# ControlBoardEspV2.net
KiCad netlist of a schematic drawn in EAGLE
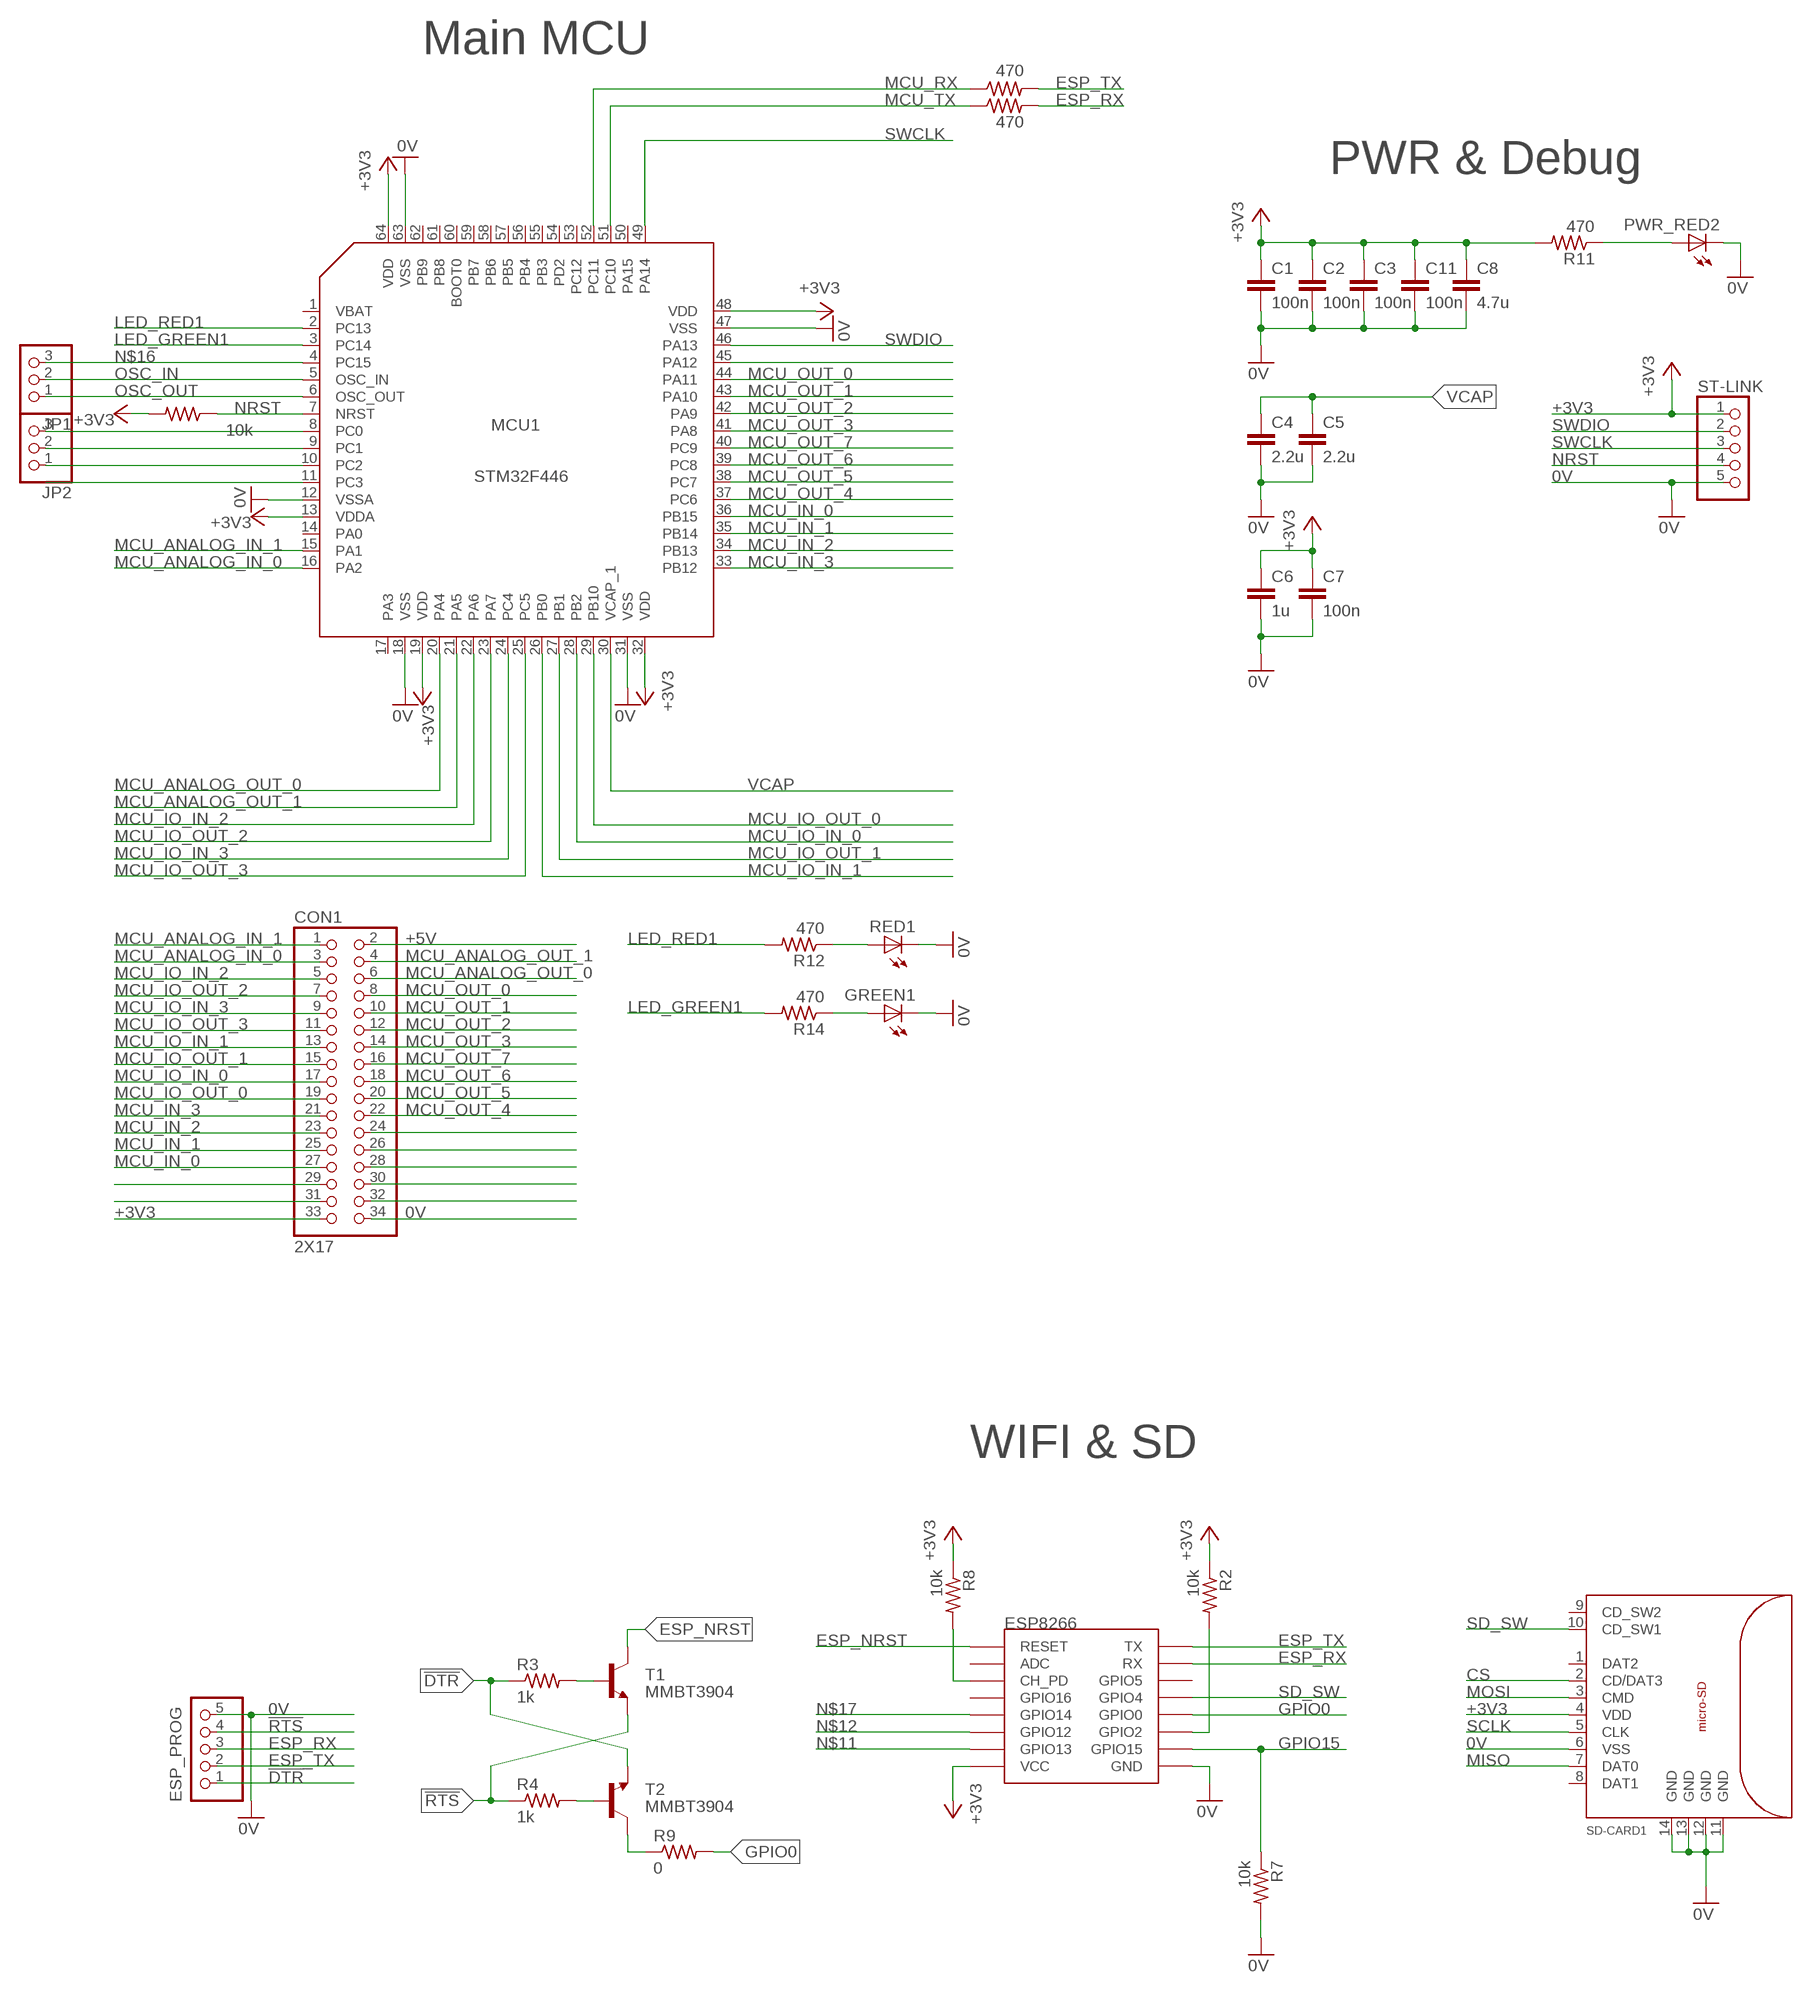
[diagram p0: schematic, sheet 1]

(export (version "E")
  (design (tool "Eeschema 10.0.6"))
  (components
    (comp (ref "C1")
      (value "100n")
      (footprint "eagle-import:C0402")
      (libsource (lib "eagle-import") (part "C-EUC0402"))
    )
    (comp (ref "C2")
      (value "100n")
      (footprint "eagle-import:C0402")
      (libsource (lib "eagle-import") (part "C-EUC0402"))
    )
    (comp (ref "C3")
      (value "100n")
      (footprint "eagle-import:C0402")
      (libsource (lib "eagle-import") (part "C-EUC0402"))
    )
    (comp (ref "C4")
      (value "2.2u")
      (footprint "eagle-import:C0402")
      (libsource (lib "eagle-import") (part "C-EUC0402"))
    )
    (comp (ref "C5")
      (value "2.2u")
      (footprint "eagle-import:C0402")
      (libsource (lib "eagle-import") (part "C-EUC0402"))
    )
    (comp (ref "C6")
      (value "1u")
      (footprint "eagle-import:C0402")
      (libsource (lib "eagle-import") (part "C-EUC0402"))
    )
    (comp (ref "C7")
      (value "100n")
      (footprint "eagle-import:C0402")
      (libsource (lib "eagle-import") (part "C-EUC0402"))
    )
    (comp (ref "C8")
      (value "4.7u")
      (footprint "eagle-import:C0402")
      (libsource (lib "eagle-import") (part "C-EUC0402"))
    )
    (comp (ref "C11")
      (value "100n")
      (footprint "eagle-import:C0402")
      (libsource (lib "eagle-import") (part "C-EUC0402"))
    )
    (comp (ref "CON1")
      (value "2X17")
      (footprint "eagle-import:2X17")
      (libsource (lib "eagle-import") (part "2X17"))
    )
    (comp (ref "ESP8266")
      (value "ESP12SMD")
      (footprint "eagle-import:ESP12-SMD")
      (libsource (lib "eagle-import") (part "ESP12SMD"))
    )
    (comp (ref "ESP_PROG")
      (value "PINHD-1X5")
      (footprint "eagle-import:1X05")
      (libsource (lib "eagle-import") (part "PINHD-1X5"))
    )
    (comp (ref "GREEN1")
      (value "LEDCHIP-LED0805")
      (footprint "eagle-import:CHIP-LED0805")
      (libsource (lib "eagle-import") (part "LEDCHIP-LED0805"))
    )
    (comp (ref "JP1")
      (value "PINHD-1X3")
      (footprint "eagle-import:1X03")
      (libsource (lib "eagle-import") (part "PINHD-1X3"))
    )
    (comp (ref "JP2")
      (value "PINHD-1X3")
      (footprint "eagle-import:1X03")
      (libsource (lib "eagle-import") (part "PINHD-1X3"))
    )
    (comp (ref "MCU1")
      (value "STM32F446")
      (footprint "eagle-import:LQFP-64")
      (libsource (lib "eagle-import") (part "STM32F446"))
    )
    (comp (ref "PWR_RED2")
      (value "LEDCHIP-LED0805")
      (footprint "eagle-import:CHIP-LED0805")
      (libsource (lib "eagle-import") (part "LEDCHIP-LED0805"))
    )
    (comp (ref "R1")
      (value "10k")
      (footprint "eagle-import:R0402")
      (libsource (lib "eagle-import") (part "R-US_R0402"))
    )
    (comp (ref "R2")
      (value "10k")
      (footprint "eagle-import:R0402")
      (libsource (lib "eagle-import") (part "R-US_R0402"))
    )
    (comp (ref "R3")
      (value "1k")
      (footprint "eagle-import:R0402")
      (libsource (lib "eagle-import") (part "R-US_R0402"))
    )
    (comp (ref "R4")
      (value "1k")
      (footprint "eagle-import:R1206")
      (libsource (lib "eagle-import") (part "R-US_R1206"))
    )
    (comp (ref "R5")
      (value "470")
      (footprint "eagle-import:R0402")
      (libsource (lib "eagle-import") (part "R-US_R0402"))
    )
    (comp (ref "R6")
      (value "470")
      (footprint "eagle-import:R0402")
      (libsource (lib "eagle-import") (part "R-US_R0402"))
    )
    (comp (ref "R7")
      (value "10k")
      (footprint "eagle-import:R0402")
      (libsource (lib "eagle-import") (part "R-US_R0402"))
    )
    (comp (ref "R8")
      (value "10k")
      (footprint "eagle-import:R0402")
      (libsource (lib "eagle-import") (part "R-US_R0402"))
    )
    (comp (ref "R9")
      (value "0")
      (footprint "eagle-import:R1206")
      (libsource (lib "eagle-import") (part "R-US_R1206"))
    )
    (comp (ref "R11")
      (value "470")
      (footprint "eagle-import:R0402")
      (libsource (lib "eagle-import") (part "R-US_R0402"))
    )
    (comp (ref "R12")
      (value "470")
      (footprint "eagle-import:R0402")
      (libsource (lib "eagle-import") (part "R-US_R0402"))
    )
    (comp (ref "R14")
      (value "470")
      (footprint "eagle-import:R0402")
      (libsource (lib "eagle-import") (part "R-US_R0402"))
    )
    (comp (ref "RED1")
      (value "LEDCHIP-LED0805")
      (footprint "eagle-import:CHIP-LED0805")
      (libsource (lib "eagle-import") (part "LEDCHIP-LED0805"))
    )
    (comp (ref "SD-CARD1")
      (value "MICRO-SD")
      (footprint "eagle-import:MICRO_SD_FOOTPRINT")
      (libsource (lib "eagle-import") (part "MICRO-SD"))
    )
    (comp (ref "ST-LINK")
      (value "PINHD-1X5")
      (footprint "eagle-import:1X05")
      (libsource (lib "eagle-import") (part "PINHD-1X5"))
    )
    (comp (ref "T1")
      (value "MMBT3904")
      (footprint "eagle-import:SOT23-BEC")
      (libsource (lib "eagle-import") (part "-NPN-SOT23-BECMMBT3904LT1"))
    )
    (comp (ref "T2")
      (value "MMBT3904")
      (footprint "eagle-import:SOT23-BEC")
      (libsource (lib "eagle-import") (part "-NPN-SOT23-BECMMBT3904LT1"))
    )
  )
  (nets
    (net (code "1") (name "+3V3") (class "Default")
      (node (ref "C1") (pin "1") (pinfunction "1_1") (pintype "passive"))
      (node (ref "C11") (pin "1") (pinfunction "1_1") (pintype "passive"))
      (node (ref "C2") (pin "1") (pinfunction "1_1") (pintype "passive"))
      (node (ref "C3") (pin "1") (pinfunction "1_1") (pintype "passive"))
      (node (ref "C6") (pin "1") (pinfunction "1_1") (pintype "passive"))
      (node (ref "C7") (pin "1") (pinfunction "1_1") (pintype "passive"))
      (node (ref "C8") (pin "1") (pinfunction "1_1") (pintype "passive"))
      (node (ref "CON1") (pin "33") (pinfunction "33_33") (pintype "passive"))
      (node (ref "ESP8266") (pin "VCC") (pinfunction "VCC_VCC") (pintype "bidirectional"))
      (node (ref "MCU1") (pin "13") (pinfunction "VDDA_13") (pintype "bidirectional"))
      (node (ref "MCU1") (pin "19") (pinfunction "VDD_19") (pintype "bidirectional"))
      (node (ref "MCU1") (pin "32") (pinfunction "VDD_32") (pintype "bidirectional"))
      (node (ref "MCU1") (pin "48") (pinfunction "VDD_48") (pintype "bidirectional"))
      (node (ref "MCU1") (pin "64") (pinfunction "VDD_64") (pintype "bidirectional"))
      (node (ref "R1") (pin "2") (pinfunction "2_2") (pintype "passive"))
      (node (ref "R11") (pin "2") (pinfunction "2_2") (pintype "passive"))
      (node (ref "R2") (pin "1") (pinfunction "1_1") (pintype "passive"))
      (node (ref "R8") (pin "1") (pinfunction "1_1") (pintype "passive"))
      (node (ref "SD-CARD1") (pin "4") (pinfunction "VDD_4") (pintype "bidirectional"))
      (node (ref "ST-LINK") (pin "1") (pinfunction "1_1") (pintype "passive"))
    )
    (net (code "2") (name "/+5V") (class "Default")
      (node (ref "CON1") (pin "2") (pinfunction "2_2") (pintype "passive"))
    )
    (net (code "3") (name "/CS") (class "Default")
      (node (ref "SD-CARD1") (pin "2") (pinfunction "CD/DAT3_2") (pintype "bidirectional"))
    )
    (net (code "4") (name "/ESP_RX") (class "Default")
      (node (ref "ESP8266") (pin "RXD0") (pinfunction "RX_RXD0") (pintype "bidirectional"))
      (node (ref "ESP_PROG") (pin "3") (pinfunction "3_3") (pintype "passive"))
      (node (ref "R6") (pin "2") (pinfunction "2_2") (pintype "passive"))
    )
    (net (code "5") (name "/ESP_TX") (class "Default")
      (node (ref "ESP8266") (pin "TXD0") (pinfunction "TX_TXD0") (pintype "bidirectional"))
      (node (ref "ESP_PROG") (pin "2") (pinfunction "2_2") (pintype "passive"))
      (node (ref "R5") (pin "2") (pinfunction "2_2") (pintype "passive"))
    )
    (net (code "6") (name "/GPIO15") (class "Default")
      (node (ref "ESP8266") (pin "GPIO15") (pinfunction "GPIO15_GPIO15") (pintype "bidirectional"))
      (node (ref "R7") (pin "1") (pinfunction "1_1") (pintype "passive"))
    )
    (net (code "7") (name "/LED_GREEN1") (class "Default")
      (node (ref "MCU1") (pin "3") (pinfunction "PC14_3") (pintype "bidirectional"))
      (node (ref "R14") (pin "2") (pinfunction "2_2") (pintype "passive"))
    )
    (net (code "8") (name "/LED_RED1") (class "Default")
      (node (ref "MCU1") (pin "2") (pinfunction "PC13_2") (pintype "bidirectional"))
      (node (ref "R12") (pin "2") (pinfunction "2_2") (pintype "passive"))
    )
    (net (code "9") (name "/MCU_ANALOG_IN_0") (class "Default")
      (node (ref "CON1") (pin "3") (pinfunction "3_3") (pintype "passive"))
      (node (ref "MCU1") (pin "16") (pinfunction "PA2_16") (pintype "bidirectional"))
    )
    (net (code "10") (name "/MCU_ANALOG_IN_1") (class "Default")
      (node (ref "CON1") (pin "1") (pinfunction "1_1") (pintype "passive"))
      (node (ref "MCU1") (pin "15") (pinfunction "PA1_15") (pintype "bidirectional"))
    )
    (net (code "11") (name "/MCU_ANALOG_OUT_0") (class "Default")
      (node (ref "CON1") (pin "6") (pinfunction "6_6") (pintype "passive"))
      (node (ref "MCU1") (pin "20") (pinfunction "PA4_20") (pintype "bidirectional"))
    )
    (net (code "12") (name "/MCU_ANALOG_OUT_1") (class "Default")
      (node (ref "CON1") (pin "4") (pinfunction "4_4") (pintype "passive"))
      (node (ref "MCU1") (pin "21") (pinfunction "PA5_21") (pintype "bidirectional"))
    )
    (net (code "13") (name "/MCU_IN_0") (class "Default")
      (node (ref "CON1") (pin "27") (pinfunction "27_27") (pintype "passive"))
      (node (ref "MCU1") (pin "36") (pinfunction "PB15_36") (pintype "bidirectional"))
    )
    (net (code "14") (name "/MCU_IN_1") (class "Default")
      (node (ref "CON1") (pin "25") (pinfunction "25_25") (pintype "passive"))
      (node (ref "MCU1") (pin "35") (pinfunction "PB14_35") (pintype "bidirectional"))
    )
    (net (code "15") (name "/MCU_IN_2") (class "Default")
      (node (ref "CON1") (pin "23") (pinfunction "23_23") (pintype "passive"))
      (node (ref "MCU1") (pin "34") (pinfunction "PB13_34") (pintype "bidirectional"))
    )
    (net (code "16") (name "/MCU_IN_3") (class "Default")
      (node (ref "CON1") (pin "21") (pinfunction "21_21") (pintype "passive"))
      (node (ref "MCU1") (pin "33") (pinfunction "PB12_33") (pintype "bidirectional"))
    )
    (net (code "17") (name "/MCU_IO_IN_0") (class "Default")
      (node (ref "CON1") (pin "17") (pinfunction "17_17") (pintype "passive"))
      (node (ref "MCU1") (pin "28") (pinfunction "PB2_28") (pintype "bidirectional"))
    )
    (net (code "18") (name "/MCU_IO_IN_1") (class "Default")
      (node (ref "CON1") (pin "13") (pinfunction "13_13") (pintype "passive"))
      (node (ref "MCU1") (pin "26") (pinfunction "PB0_26") (pintype "bidirectional"))
    )
    (net (code "19") (name "/MCU_IO_IN_2") (class "Default")
      (node (ref "CON1") (pin "5") (pinfunction "5_5") (pintype "passive"))
      (node (ref "MCU1") (pin "22") (pinfunction "PA6_22") (pintype "bidirectional"))
    )
    (net (code "20") (name "/MCU_IO_IN_3") (class "Default")
      (node (ref "CON1") (pin "9") (pinfunction "9_9") (pintype "passive"))
      (node (ref "MCU1") (pin "24") (pinfunction "PC4_24") (pintype "bidirectional"))
    )
    (net (code "21") (name "/MCU_IO_OUT_0") (class "Default")
      (node (ref "CON1") (pin "19") (pinfunction "19_19") (pintype "passive"))
      (node (ref "MCU1") (pin "29") (pinfunction "PB10_29") (pintype "bidirectional"))
    )
    (net (code "22") (name "/MCU_IO_OUT_1") (class "Default")
      (node (ref "CON1") (pin "15") (pinfunction "15_15") (pintype "passive"))
      (node (ref "MCU1") (pin "27") (pinfunction "PB1_27") (pintype "bidirectional"))
    )
    (net (code "23") (name "/MCU_IO_OUT_2") (class "Default")
      (node (ref "CON1") (pin "7") (pinfunction "7_7") (pintype "passive"))
      (node (ref "MCU1") (pin "23") (pinfunction "PA7_23") (pintype "bidirectional"))
    )
    (net (code "24") (name "/MCU_IO_OUT_3") (class "Default")
      (node (ref "CON1") (pin "11") (pinfunction "11_11") (pintype "passive"))
      (node (ref "MCU1") (pin "25") (pinfunction "PC5_25") (pintype "bidirectional"))
    )
    (net (code "25") (name "/MCU_OUT_0") (class "Default")
      (node (ref "CON1") (pin "8") (pinfunction "8_8") (pintype "passive"))
      (node (ref "MCU1") (pin "44") (pinfunction "PA11_44") (pintype "bidirectional"))
    )
    (net (code "26") (name "/MCU_OUT_1") (class "Default")
      (node (ref "CON1") (pin "10") (pinfunction "10_10") (pintype "passive"))
      (node (ref "MCU1") (pin "43") (pinfunction "PA10_43") (pintype "bidirectional"))
    )
    (net (code "27") (name "/MCU_OUT_2") (class "Default")
      (node (ref "CON1") (pin "12") (pinfunction "12_12") (pintype "passive"))
      (node (ref "MCU1") (pin "42") (pinfunction "PA9_42") (pintype "bidirectional"))
    )
    (net (code "28") (name "/MCU_OUT_3") (class "Default")
      (node (ref "CON1") (pin "14") (pinfunction "14_14") (pintype "passive"))
      (node (ref "MCU1") (pin "41") (pinfunction "PA8_41") (pintype "bidirectional"))
    )
    (net (code "29") (name "/MCU_OUT_4") (class "Default")
      (node (ref "CON1") (pin "22") (pinfunction "22_22") (pintype "passive"))
      (node (ref "MCU1") (pin "37") (pinfunction "PC6_37") (pintype "bidirectional"))
    )
    (net (code "30") (name "/MCU_OUT_5") (class "Default")
      (node (ref "CON1") (pin "20") (pinfunction "20_20") (pintype "passive"))
      (node (ref "MCU1") (pin "38") (pinfunction "PC7_38") (pintype "bidirectional"))
    )
    (net (code "31") (name "/MCU_OUT_6") (class "Default")
      (node (ref "CON1") (pin "18") (pinfunction "18_18") (pintype "passive"))
      (node (ref "MCU1") (pin "39") (pinfunction "PC8_39") (pintype "bidirectional"))
    )
    (net (code "32") (name "/MCU_OUT_7") (class "Default")
      (node (ref "CON1") (pin "16") (pinfunction "16_16") (pintype "passive"))
      (node (ref "MCU1") (pin "40") (pinfunction "PC9_40") (pintype "bidirectional"))
    )
    (net (code "33") (name "/MCU_RX") (class "Default")
      (node (ref "MCU1") (pin "52") (pinfunction "PC11_52") (pintype "bidirectional"))
      (node (ref "R5") (pin "1") (pinfunction "1_1") (pintype "passive"))
    )
    (net (code "34") (name "/MCU_TX") (class "Default")
      (node (ref "MCU1") (pin "51") (pinfunction "PC10_51") (pintype "bidirectional"))
      (node (ref "R6") (pin "1") (pinfunction "1_1") (pintype "passive"))
    )
    (net (code "35") (name "/MISO") (class "Default")
      (node (ref "SD-CARD1") (pin "7") (pinfunction "DAT0_7") (pintype "bidirectional"))
    )
    (net (code "36") (name "/MOSI") (class "Default")
      (node (ref "SD-CARD1") (pin "3") (pinfunction "CMD_3") (pintype "bidirectional"))
    )
    (net (code "37") (name "/N$11") (class "Default")
      (node (ref "ESP8266") (pin "GPIO13") (pinfunction "GPIO13_GPIO13") (pintype "bidirectional"))
    )
    (net (code "38") (name "/N$12") (class "Default")
      (node (ref "ESP8266") (pin "GPIO12") (pinfunction "GPIO12_GPIO12") (pintype "bidirectional"))
    )
    (net (code "39") (name "/N$16") (class "Default")
      (node (ref "JP1") (pin "3") (pinfunction "3_3") (pintype "passive"))
      (node (ref "MCU1") (pin "4") (pinfunction "PC15_4") (pintype "bidirectional"))
    )
    (net (code "40") (name "/N$17") (class "Default")
      (node (ref "ESP8266") (pin "GPIO14") (pinfunction "GPIO14_GPIO14") (pintype "bidirectional"))
    )
    (net (code "41") (name "/NRST") (class "Default")
      (node (ref "MCU1") (pin "7") (pinfunction "NRST_7") (pintype "bidirectional"))
      (node (ref "R1") (pin "1") (pinfunction "1_1") (pintype "passive"))
      (node (ref "ST-LINK") (pin "4") (pinfunction "4_4") (pintype "passive"))
    )
    (net (code "42") (name "/OSC_IN") (class "Default")
      (node (ref "JP1") (pin "2") (pinfunction "2_2") (pintype "passive"))
      (node (ref "MCU1") (pin "5") (pinfunction "OSC_IN_5") (pintype "bidirectional"))
    )
    (net (code "43") (name "/OSC_OUT") (class "Default")
      (node (ref "JP1") (pin "1") (pinfunction "1_1") (pintype "passive"))
      (node (ref "MCU1") (pin "6") (pinfunction "OSC_OUT_6") (pintype "bidirectional"))
    )
    (net (code "44") (name "/SCLK") (class "Default")
      (node (ref "SD-CARD1") (pin "5") (pinfunction "CLK_5") (pintype "bidirectional"))
    )
    (net (code "45") (name "/SD_SW") (class "Default")
      (node (ref "ESP8266") (pin "GPIO5") (pinfunction "GPIO4_GPIO5") (pintype "bidirectional"))
      (node (ref "SD-CARD1") (pin "10") (pinfunction "CD_SW1_10") (pintype "bidirectional"))
    )
    (net (code "46") (name "/SWCLK") (class "Default")
      (node (ref "MCU1") (pin "49") (pinfunction "PA14_49") (pintype "bidirectional"))
      (node (ref "ST-LINK") (pin "3") (pinfunction "3_3") (pintype "passive"))
    )
    (net (code "47") (name "/SWDIO") (class "Default")
      (node (ref "MCU1") (pin "46") (pinfunction "PA13_46") (pintype "bidirectional"))
      (node (ref "ST-LINK") (pin "2") (pinfunction "2_2") (pintype "passive"))
    )
    (net (code "48") (name "/~{DTR}") (class "Default")
      (node (ref "ESP_PROG") (pin "1") (pinfunction "1_1") (pintype "passive"))
      (node (ref "R3") (pin "1") (pinfunction "1_1") (pintype "passive"))
      (node (ref "T2") (pin "E") (pinfunction "E_E") (pintype "passive"))
    )
    (net (code "49") (name "/~{RTS}") (class "Default")
      (node (ref "ESP_PROG") (pin "4") (pinfunction "4_4") (pintype "passive"))
      (node (ref "R4") (pin "1") (pinfunction "1_1") (pintype "passive"))
      (node (ref "T1") (pin "E") (pinfunction "E_E") (pintype "passive"))
    )
    (net (code "50") (name "0V") (class "Default")
      (node (ref "C1") (pin "2") (pinfunction "2_2") (pintype "passive"))
      (node (ref "C11") (pin "2") (pinfunction "2_2") (pintype "passive"))
      (node (ref "C2") (pin "2") (pinfunction "2_2") (pintype "passive"))
      (node (ref "C3") (pin "2") (pinfunction "2_2") (pintype "passive"))
      (node (ref "C4") (pin "2") (pinfunction "2_2") (pintype "passive"))
      (node (ref "C5") (pin "2") (pinfunction "2_2") (pintype "passive"))
      (node (ref "C6") (pin "2") (pinfunction "2_2") (pintype "passive"))
      (node (ref "C7") (pin "2") (pinfunction "2_2") (pintype "passive"))
      (node (ref "C8") (pin "2") (pinfunction "2_2") (pintype "passive"))
      (node (ref "CON1") (pin "34") (pinfunction "34_34") (pintype "passive"))
      (node (ref "ESP8266") (pin "GND") (pinfunction "GND_GND") (pintype "bidirectional"))
      (node (ref "ESP_PROG") (pin "5") (pinfunction "5_5") (pintype "passive"))
      (node (ref "GREEN1") (pin "C") (pinfunction "C_C") (pintype "passive"))
      (node (ref "MCU1") (pin "12") (pinfunction "VSSA_12") (pintype "bidirectional"))
      (node (ref "MCU1") (pin "18") (pinfunction "VSS_18") (pintype "bidirectional"))
      (node (ref "MCU1") (pin "31") (pinfunction "VSS_31") (pintype "bidirectional"))
      (node (ref "MCU1") (pin "47") (pinfunction "VSS_47") (pintype "bidirectional"))
      (node (ref "MCU1") (pin "63") (pinfunction "VSS_63") (pintype "bidirectional"))
      (node (ref "PWR_RED2") (pin "C") (pinfunction "C_C") (pintype "passive"))
      (node (ref "R7") (pin "2") (pinfunction "2_2") (pintype "passive"))
      (node (ref "RED1") (pin "C") (pinfunction "C_C") (pintype "passive"))
      (node (ref "SD-CARD1") (pin "11") (pinfunction "GND_11") (pintype "bidirectional"))
      (node (ref "SD-CARD1") (pin "12") (pinfunction "GND_12") (pintype "bidirectional"))
      (node (ref "SD-CARD1") (pin "13") (pinfunction "GND_13") (pintype "bidirectional"))
      (node (ref "SD-CARD1") (pin "14") (pinfunction "GND_14") (pintype "bidirectional"))
      (node (ref "SD-CARD1") (pin "6") (pinfunction "VSS_6") (pintype "bidirectional"))
      (node (ref "ST-LINK") (pin "5") (pinfunction "5_5") (pintype "passive"))
    )
    (net (code "51") (name "ESP_NRST") (class "Default")
      (node (ref "ESP8266") (pin "RESET") (pinfunction "RESET_RESET") (pintype "bidirectional"))
      (node (ref "T1") (pin "C") (pinfunction "C_C") (pintype "passive"))
    )
    (net (code "52") (name "GPIO0") (class "Default")
      (node (ref "ESP8266") (pin "GPIO0") (pinfunction "GPIO0_GPIO0") (pintype "bidirectional"))
      (node (ref "R9") (pin "2") (pinfunction "2_2") (pintype "passive"))
    )
    (net (code "53") (name "Net-(ESP8266-PadCH_PD)") (class "Default")
      (node (ref "ESP8266") (pin "CH_PD") (pinfunction "CH_PD_CH_PD") (pintype "bidirectional"))
      (node (ref "R8") (pin "2") (pinfunction "2_2") (pintype "passive"))
    )
    (net (code "54") (name "Net-(ESP8266-PadGPIO2)") (class "Default")
      (node (ref "ESP8266") (pin "GPIO2") (pinfunction "GPIO2_GPIO2") (pintype "bidirectional"))
      (node (ref "R2") (pin "2") (pinfunction "2_2") (pintype "passive"))
    )
    (net (code "55") (name "Net-(GREEN1-PadA)") (class "Default")
      (node (ref "GREEN1") (pin "A") (pinfunction "A_A") (pintype "passive"))
      (node (ref "R14") (pin "1") (pinfunction "1_1") (pintype "passive"))
    )
    (net (code "56") (name "Net-(MCU1-PC0)") (class "Default")
      (node (ref "JP2") (pin "3") (pinfunction "3_3") (pintype "passive"))
      (node (ref "MCU1") (pin "8") (pinfunction "PC0_8") (pintype "bidirectional"))
    )
    (net (code "57") (name "Net-(MCU1-PC1)") (class "Default")
      (node (ref "JP2") (pin "2") (pinfunction "2_2") (pintype "passive"))
      (node (ref "MCU1") (pin "9") (pinfunction "PC1_9") (pintype "bidirectional"))
    )
    (net (code "58") (name "Net-(MCU1-PC2)") (class "Default")
      (node (ref "JP2") (pin "1") (pinfunction "1_1") (pintype "passive"))
      (node (ref "MCU1") (pin "10") (pinfunction "PC2_10") (pintype "bidirectional"))
    )
    (net (code "59") (name "Net-(PWR_RED2-PadA)") (class "Default")
      (node (ref "PWR_RED2") (pin "A") (pinfunction "A_A") (pintype "passive"))
      (node (ref "R11") (pin "1") (pinfunction "1_1") (pintype "passive"))
    )
    (net (code "60") (name "Net-(R3-Pad2)") (class "Default")
      (node (ref "R3") (pin "2") (pinfunction "2_2") (pintype "passive"))
      (node (ref "T1") (pin "B") (pinfunction "B_B") (pintype "passive"))
    )
    (net (code "61") (name "Net-(R4-Pad2)") (class "Default")
      (node (ref "R4") (pin "2") (pinfunction "2_2") (pintype "passive"))
      (node (ref "T2") (pin "B") (pinfunction "B_B") (pintype "passive"))
    )
    (net (code "62") (name "Net-(R9-Pad1)") (class "Default")
      (node (ref "R9") (pin "1") (pinfunction "1_1") (pintype "passive"))
      (node (ref "T2") (pin "C") (pinfunction "C_C") (pintype "passive"))
    )
    (net (code "63") (name "Net-(R12-Pad1)") (class "Default")
      (node (ref "R12") (pin "1") (pinfunction "1_1") (pintype "passive"))
      (node (ref "RED1") (pin "A") (pinfunction "A_A") (pintype "passive"))
    )
    (net (code "64") (name "VCAP") (class "Default")
      (node (ref "C4") (pin "1") (pinfunction "1_1") (pintype "passive"))
      (node (ref "C5") (pin "1") (pinfunction "1_1") (pintype "passive"))
      (node (ref "MCU1") (pin "30") (pinfunction "VCAP_1_30") (pintype "bidirectional"))
    )
    (net (code "65") (name "unconnected-(CON1-Pad24)") (class "Default")
      (node (ref "CON1") (pin "24") (pinfunction "24_24") (pintype "passive"))
    )
    (net (code "66") (name "unconnected-(CON1-Pad26)") (class "Default")
      (node (ref "CON1") (pin "26") (pinfunction "26_26") (pintype "passive"))
    )
    (net (code "67") (name "unconnected-(CON1-Pad28)") (class "Default")
      (node (ref "CON1") (pin "28") (pinfunction "28_28") (pintype "passive"))
    )
    (net (code "68") (name "unconnected-(CON1-Pad29)") (class "Default")
      (node (ref "CON1") (pin "29") (pinfunction "29_29") (pintype "passive"))
    )
    (net (code "69") (name "unconnected-(CON1-Pad30)") (class "Default")
      (node (ref "CON1") (pin "30") (pinfunction "30_30") (pintype "passive"))
    )
    (net (code "70") (name "unconnected-(CON1-Pad31)") (class "Default")
      (node (ref "CON1") (pin "31") (pinfunction "31_31") (pintype "passive"))
    )
    (net (code "71") (name "unconnected-(CON1-Pad32)") (class "Default")
      (node (ref "CON1") (pin "32") (pinfunction "32_32") (pintype "passive"))
    )
    (net (code "72") (name "unconnected-(ESP8266-GPIO5-PadGPIO4)") (class "Default")
      (node (ref "ESP8266") (pin "GPIO4") (pinfunction "GPIO5_GPIO4") (pintype "bidirectional"))
    )
    (net (code "73") (name "unconnected-(ESP8266-PadADC)") (class "Default")
      (node (ref "ESP8266") (pin "ADC") (pinfunction "ADC_ADC") (pintype "bidirectional"))
    )
    (net (code "74") (name "unconnected-(ESP8266-PadGPIO16)") (class "Default")
      (node (ref "ESP8266") (pin "GPIO16") (pinfunction "GPIO16_GPIO16") (pintype "bidirectional"))
    )
    (net (code "75") (name "unconnected-(MCU1-BOOT0-Pad60)") (class "Default")
      (node (ref "MCU1") (pin "60") (pinfunction "BOOT0_60") (pintype "bidirectional"))
    )
    (net (code "76") (name "unconnected-(MCU1-PA0-Pad14)") (class "Default")
      (node (ref "MCU1") (pin "14") (pinfunction "PA0_14") (pintype "bidirectional"))
    )
    (net (code "77") (name "unconnected-(MCU1-PA3-Pad17)") (class "Default")
      (node (ref "MCU1") (pin "17") (pinfunction "PA3_17") (pintype "bidirectional"))
    )
    (net (code "78") (name "unconnected-(MCU1-PA12-Pad45)") (class "Default")
      (node (ref "MCU1") (pin "45") (pinfunction "PA12_45") (pintype "bidirectional"))
    )
    (net (code "79") (name "unconnected-(MCU1-PA15-Pad50)") (class "Default")
      (node (ref "MCU1") (pin "50") (pinfunction "PA15_50") (pintype "bidirectional"))
    )
    (net (code "80") (name "unconnected-(MCU1-PB3-Pad55)") (class "Default")
      (node (ref "MCU1") (pin "55") (pinfunction "PB3_55") (pintype "bidirectional"))
    )
    (net (code "81") (name "unconnected-(MCU1-PB4-Pad56)") (class "Default")
      (node (ref "MCU1") (pin "56") (pinfunction "PB4_56") (pintype "bidirectional"))
    )
    (net (code "82") (name "unconnected-(MCU1-PB5-Pad57)") (class "Default")
      (node (ref "MCU1") (pin "57") (pinfunction "PB5_57") (pintype "bidirectional"))
    )
    (net (code "83") (name "unconnected-(MCU1-PB6-Pad58)") (class "Default")
      (node (ref "MCU1") (pin "58") (pinfunction "PB6_58") (pintype "bidirectional"))
    )
    (net (code "84") (name "unconnected-(MCU1-PB7-Pad59)") (class "Default")
      (node (ref "MCU1") (pin "59") (pinfunction "PB7_59") (pintype "bidirectional"))
    )
    (net (code "85") (name "unconnected-(MCU1-PB8-Pad61)") (class "Default")
      (node (ref "MCU1") (pin "61") (pinfunction "PB8_61") (pintype "bidirectional"))
    )
    (net (code "86") (name "unconnected-(MCU1-PB9-Pad62)") (class "Default")
      (node (ref "MCU1") (pin "62") (pinfunction "PB9_62") (pintype "bidirectional"))
    )
    (net (code "87") (name "unconnected-(MCU1-PC3-Pad11)") (class "Default")
      (node (ref "MCU1") (pin "11") (pinfunction "PC3_11") (pintype "bidirectional"))
    )
    (net (code "88") (name "unconnected-(MCU1-PC12-Pad53)") (class "Default")
      (node (ref "MCU1") (pin "53") (pinfunction "PC12_53") (pintype "bidirectional"))
    )
    (net (code "89") (name "unconnected-(MCU1-PD2-Pad54)") (class "Default")
      (node (ref "MCU1") (pin "54") (pinfunction "PD2_54") (pintype "bidirectional"))
    )
    (net (code "90") (name "unconnected-(MCU1-VBAT-Pad1)") (class "Default")
      (node (ref "MCU1") (pin "1") (pinfunction "VBAT_1") (pintype "bidirectional"))
    )
    (net (code "91") (name "unconnected-(SD-CARD1-CD_SW2-Pad9)") (class "Default")
      (node (ref "SD-CARD1") (pin "9") (pinfunction "CD_SW2_9") (pintype "bidirectional"))
    )
    (net (code "92") (name "unconnected-(SD-CARD1-DAT1-Pad8)") (class "Default")
      (node (ref "SD-CARD1") (pin "8") (pinfunction "DAT1_8") (pintype "bidirectional"))
    )
    (net (code "93") (name "unconnected-(SD-CARD1-DAT2-Pad1)") (class "Default")
      (node (ref "SD-CARD1") (pin "1") (pinfunction "DAT2_1") (pintype "bidirectional"))
    )
  )
)
